# connect_board.net
KiCad netlist of a schematic drawn in Altium Designer
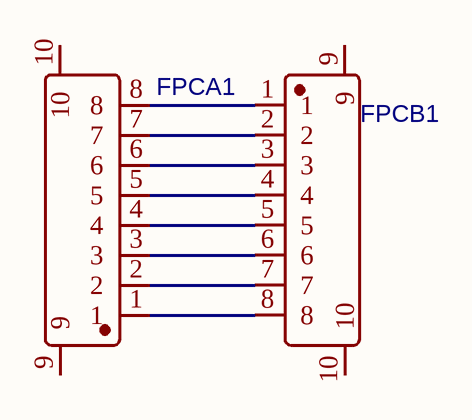
[diagram p0: connect_board.SchDoc]

(export (version "E")
  (design (tool "Eeschema 10.0.6"))
  (components
    (comp (ref "FPCA1")
      (value "FFC 05 8P")
      (footprint "FFC-SMD_8P-P0.50")
      (fields
        (field (name "MANUFACTURER") "TXGA(特思嘉)")
        (field (name "MANUFACTURER PART") "FFC05001-08SBB124W5M-H")
        (field (name "CONTRIBUTOR") "LCSC")
      )
      (libsource (lib "Connectors") (part "FFC 05 8P"))
    )
    (comp (ref "FPCB1")
      (value "FFC 05 8P")
      (footprint "FFC-SMD_8P-P0.50")
      (fields
        (field (name "MANUFACTURER") "TXGA(特思嘉)")
        (field (name "MANUFACTURER PART") "FFC05001-08SBB124W5M-H")
        (field (name "CONTRIBUTOR") "LCSC")
      )
      (libsource (lib "Connectors") (part "FFC 05 8P"))
    )
  )
  (nets
    (net (code "1") (name "Net-(FPCA1-Pad1)") (class "Default")
      (node (ref "FPCA1") (pin "1") (pinfunction "1_1") (pintype "passive"))
      (node (ref "FPCB1") (pin "8") (pinfunction "8_8") (pintype "passive"))
    )
    (net (code "2") (name "Net-(FPCA1-Pad2)") (class "Default")
      (node (ref "FPCA1") (pin "2") (pinfunction "2_2") (pintype "passive"))
      (node (ref "FPCB1") (pin "7") (pinfunction "7_7") (pintype "passive"))
    )
    (net (code "3") (name "Net-(FPCA1-Pad3)") (class "Default")
      (node (ref "FPCA1") (pin "3") (pinfunction "3_3") (pintype "passive"))
      (node (ref "FPCB1") (pin "6") (pinfunction "6_6") (pintype "passive"))
    )
    (net (code "4") (name "Net-(FPCA1-Pad4)") (class "Default")
      (node (ref "FPCA1") (pin "4") (pinfunction "4_4") (pintype "passive"))
      (node (ref "FPCB1") (pin "5") (pinfunction "5_5") (pintype "passive"))
    )
    (net (code "5") (name "Net-(FPCA1-Pad5)") (class "Default")
      (node (ref "FPCA1") (pin "5") (pinfunction "5_5") (pintype "passive"))
      (node (ref "FPCB1") (pin "4") (pinfunction "4_4") (pintype "passive"))
    )
    (net (code "6") (name "Net-(FPCA1-Pad6)") (class "Default")
      (node (ref "FPCA1") (pin "6") (pinfunction "6_6") (pintype "passive"))
      (node (ref "FPCB1") (pin "3") (pinfunction "3_3") (pintype "passive"))
    )
    (net (code "7") (name "Net-(FPCA1-Pad7)") (class "Default")
      (node (ref "FPCA1") (pin "7") (pinfunction "7_7") (pintype "passive"))
      (node (ref "FPCB1") (pin "2") (pinfunction "2_2") (pintype "passive"))
    )
    (net (code "8") (name "Net-(FPCA1-Pad8)") (class "Default")
      (node (ref "FPCA1") (pin "8") (pinfunction "8_8") (pintype "passive"))
      (node (ref "FPCB1") (pin "1") (pinfunction "1_1") (pintype "passive"))
    )
    (net (code "9") (name "unconnected-(FPCA1-Pad9)") (class "Default")
      (node (ref "FPCA1") (pin "9") (pinfunction "9_9") (pintype "passive"))
    )
    (net (code "10") (name "unconnected-(FPCA1-Pad10)") (class "Default")
      (node (ref "FPCA1") (pin "10") (pinfunction "10_10") (pintype "passive"))
    )
    (net (code "11") (name "unconnected-(FPCB1-Pad9)") (class "Default")
      (node (ref "FPCB1") (pin "9") (pinfunction "9_9") (pintype "passive"))
    )
    (net (code "12") (name "unconnected-(FPCB1-Pad10)") (class "Default")
      (node (ref "FPCB1") (pin "10") (pinfunction "10_10") (pintype "passive"))
    )
  )
)
